# oscilador_10MHz.net
KiCad netlist of a schematic drawn in Altium Designer
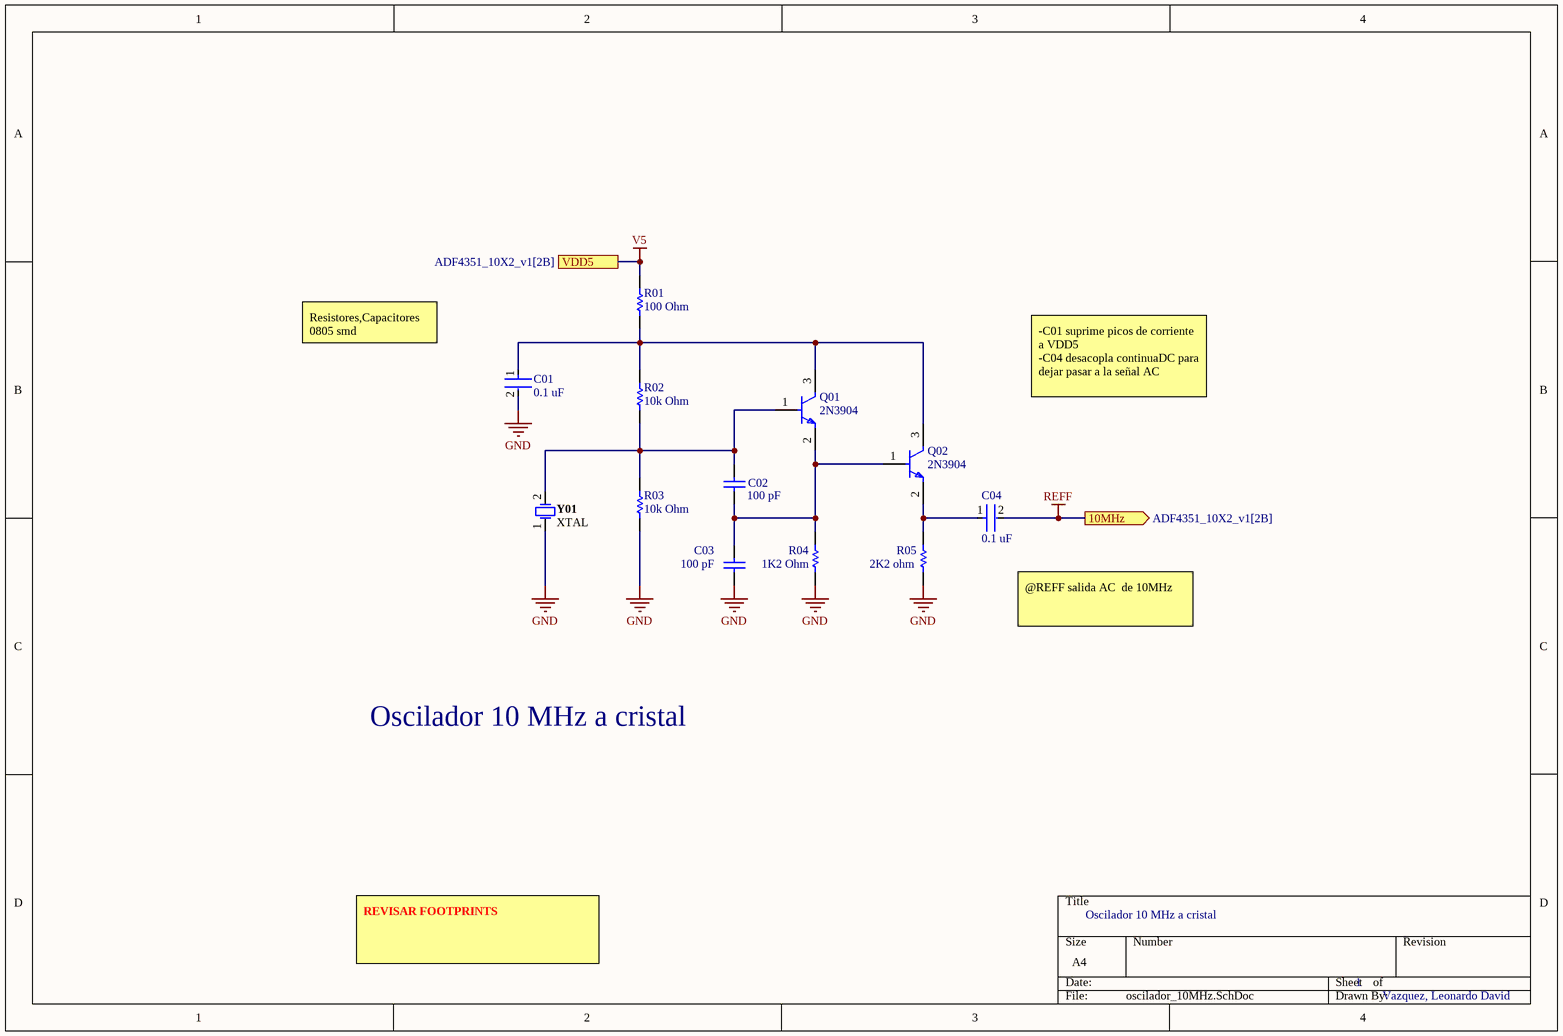
[diagram p0: oscilador_10MHz.SchDoc]

(export (version "E")
  (design (tool "Eeschema 10.0.6"))
  (components
    (comp (ref "C01")
      (value "0.1 uF")
      (footprint "FP-CC0805-0_85-MFG")
      (description "CAP CER 0.1UF 50V X7R 0805")
      (fields (field (name "TOLERANCE") "0.1") (field (name "MANUFACTURER PART NUMBER") "CC0805KRX7R9BB104"))
      (libsource (lib "Altium Content Vault") (part "11868f565c42a9108669ba33697ecf6"))
    )
    (comp (ref "C02")
      (value "100 pF")
      (footprint "CAPC2013X88X50ML20T25")
      (fields (field (name "MANUFACTURER") "Kemet") (field (name "PART NUMBER") "C0805C101JCGACTU"))
      (libsource (lib "Altium Content Vault") (part "CAP"))
    )
    (comp (ref "C03")
      (value "100 pF")
      (footprint "CAPC2013X88X50ML20T25")
      (fields (field (name "MANUFACTURER") "Kemet") (field (name "PART NUMBER") "C0805C101JCGACTU"))
      (libsource (lib "Altium Content Vault") (part "CAP"))
    )
    (comp (ref "C04")
      (value "0.1 uF")
      (footprint "FP-CC0805-0_85-MFG")
      (description "CAP CER 0.1UF 50V X7R 0805")
      (fields (field (name "TOLERANCE") "0.1") (field (name "MANUFACTURER PART NUMBER") "CC0805KRX7R9BB104"))
      (libsource (lib "Altium Content Vault") (part "11868f565c42a9108669ba33697ecf6"))
    )
    (comp (ref "Q01")
      (value "2N3904")
      (footprint "FP-SOT23-IPC_A")
      (description "TRANS NPN 40V 0.6A SMD SOT23-3")
      (fields (field (name "VOLTAGE") "40V"))
      (libsource (lib "Altium Content Vault") (part "b44e953556f554d0102664c7d152cb4"))
    )
    (comp (ref "Q02")
      (value "2N3904")
      (footprint "FP-SOT23-IPC_A")
      (description "TRANS NPN 40V 0.6A SMD SOT23-3")
      (fields (field (name "VOLTAGE") "40V"))
      (libsource (lib "Altium Content Vault") (part "b44e953556f554d0102664c7d152cb4"))
    )
    (comp (ref "R01")
      (value "100 Ohm")
      (footprint "RESC2013X60X40ML20T25")
      (fields (field (name "MANUFACTURER") "Panasonic") (field (name "PART NUMBER") "ERA6AEB101V"))
      (libsource (lib "Altium Content Vault") (part "RES"))
    )
    (comp (ref "R02")
      (value "10k Ohm")
      (footprint "RESC2013X60X35NL10T20")
      (description "Chip Resistor, 10 KOhm, +/- 1%, 0.125 W, -55 to 155 degC, 0805 (2012 Metric), RoHS, Tape and Reel")
      (fields (field (name "MANUFACTURER") "Yageo"))
      (libsource (lib "Altium Content Vault") (part "RES-2"))
    )
    (comp (ref "R03")
      (value "10k Ohm")
      (footprint "RESC2013X60X35NL10T20")
      (description "Chip Resistor, 10 KOhm, +/- 1%, 0.125 W, -55 to 155 degC, 0805 (2012 Metric), RoHS, Tape and Reel")
      (fields (field (name "MANUFACTURER") "Yageo"))
      (libsource (lib "Altium Content Vault") (part "RES-2"))
    )
    (comp (ref "R04")
      (value "1K2 Ohm")
      (footprint "RESC2013X70X40NL20T20")
      (description "Chip Resistor, 120 Ohm, +/- 1%, 0.125 W, -55 to 155 degC, 0805 (2012 Metric), RoHS, Tape and Reel")
      (fields (field (name "MANUFACTURER") "Panasonic"))
      (libsource (lib "Altium Content Vault") (part "RES-2"))
    )
    (comp (ref "R05")
      (value "2K2 ohm")
      (footprint "RESC2013X70X40NL20T20")
      (description "Chip Resistor, 120 Ohm, +/- 1%, 0.125 W, -55 to 155 degC, 0805 (2012 Metric), RoHS, Tape and Reel")
      (fields (field (name "MANUFACTURER") "Panasonic"))
      (libsource (lib "Altium Content Vault") (part "RES-2"))
    )
    (comp (ref "Y01")
      (value "XTAL")
      (footprint "Cristal mini")
      (description "Resistance Weld Thru-Hole Crystal, 16 MHz, -20 to 70 degC, 2-Pin THD, RoHS, Bulk")
      (fields (field (name "TOLERANCE") "1%"))
      (libsource (lib "Altium Content Vault") (part "XTAL-1-2-2"))
    )
  )
  (nets
    (net (code "1") (name "GND") (class "Default")
      (node (ref "C01") (pin "2") (pinfunction "2_2") (pintype "passive"))
      (node (ref "C03") (pin "1") (pinfunction "1_1") (pintype "passive"))
      (node (ref "R03") (pin "1") (pinfunction "1_1") (pintype "passive"))
      (node (ref "R04") (pin "1") (pinfunction "1_1") (pintype "passive"))
      (node (ref "R05") (pin "1") (pinfunction "1_1") (pintype "passive"))
      (node (ref "Y01") (pin "1") (pinfunction "1_1") (pintype "passive"))
    )
    (net (code "2") (name "Net-(Q01-B)") (class "Default")
      (node (ref "C02") (pin "2") (pinfunction "2_2") (pintype "passive"))
      (node (ref "Q01") (pin "1") (pinfunction "B_1") (pintype "passive"))
      (node (ref "R02") (pin "1") (pinfunction "1_1") (pintype "passive"))
      (node (ref "R03") (pin "2") (pinfunction "2_2") (pintype "passive"))
      (node (ref "Y01") (pin "2") (pinfunction "2_2") (pintype "passive"))
    )
    (net (code "3") (name "Net-(Q01-C)") (class "Default")
      (node (ref "C01") (pin "1") (pinfunction "1_1") (pintype "passive"))
      (node (ref "Q01") (pin "3") (pinfunction "C_3") (pintype "passive"))
      (node (ref "Q02") (pin "3") (pinfunction "C_3") (pintype "passive"))
      (node (ref "R01") (pin "1") (pinfunction "1_1") (pintype "passive"))
      (node (ref "R02") (pin "2") (pinfunction "2_2") (pintype "passive"))
    )
    (net (code "4") (name "Net-(Q01-E)") (class "Default")
      (node (ref "C02") (pin "1") (pinfunction "1_1") (pintype "passive"))
      (node (ref "C03") (pin "2") (pinfunction "2_2") (pintype "passive"))
      (node (ref "Q01") (pin "2") (pinfunction "E_2") (pintype "passive"))
      (node (ref "Q02") (pin "1") (pinfunction "B_1") (pintype "passive"))
      (node (ref "R04") (pin "2") (pinfunction "2_2") (pintype "passive"))
    )
    (net (code "5") (name "Net-(Q02-E)") (class "Default")
      (node (ref "C04") (pin "1") (pinfunction "1_1") (pintype "passive"))
      (node (ref "Q02") (pin "2") (pinfunction "E_2") (pintype "passive"))
      (node (ref "R05") (pin "2") (pinfunction "2_2") (pintype "passive"))
    )
    (net (code "6") (name "REFF") (class "Default")
      (node (ref "C04") (pin "2") (pinfunction "2_2") (pintype "passive"))
    )
    (net (code "7") (name "V5") (class "Default")
      (node (ref "R01") (pin "2") (pinfunction "2_2") (pintype "passive"))
    )
  )
)
